# Audio_Codec.net
KiCad netlist of a schematic drawn in Altium Designer
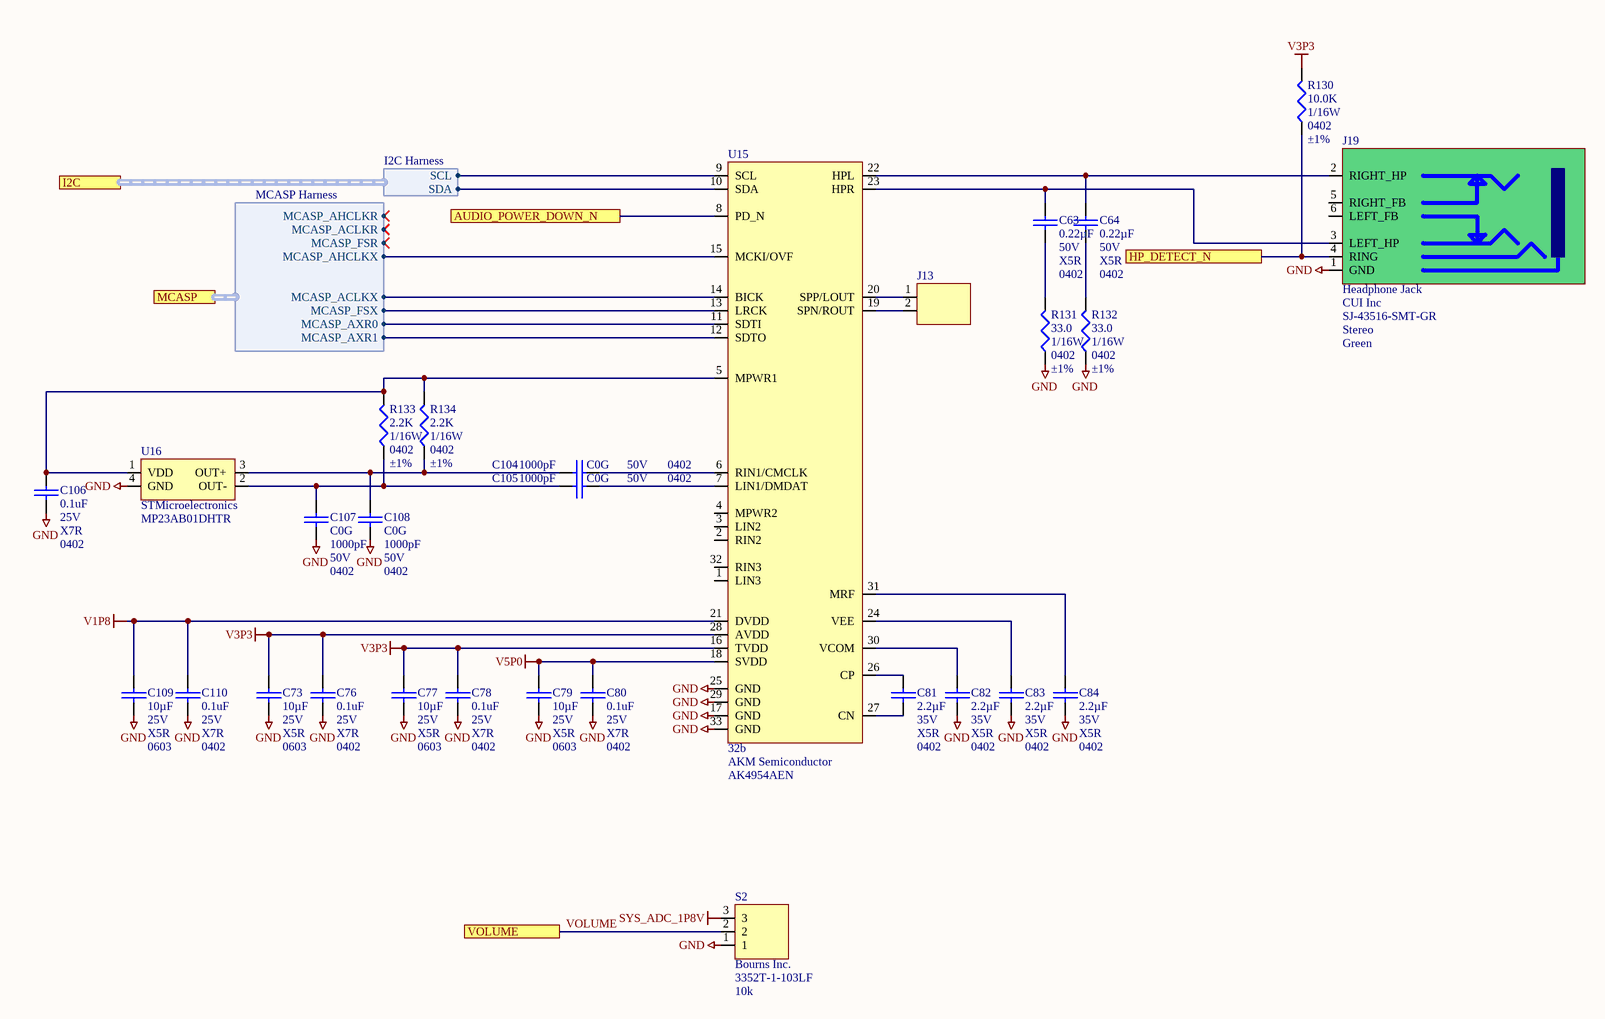
[diagram p0: Audio Codec.SchDoc]

(export (version "E")
  (design (tool "Eeschema 10.0.6"))
  (components
    (comp (ref "C63")
      (value "C_0402_0.22UF_50V")
      (footprint "C_0402")
      (description "CAP CER 0.22UF 50V X5R 0402")
      (fields
        (field (name "MANUFACTURER") "Taiyo Yuden")
        (field (name "MANUFACTURER PART NUMBER") "UMK105BJ224KV-F")
        (field (name "CAPACITANCE") "0.22µF")
        (field (name "VOLTAGE - RATED") "50V")
        (field (name "TEMPERATURE COEFFICIENT") "X5R")
        (field (name "PACKAGE / CASE") "0402")
      )
      (libsource (lib "Main Library") (part "C_0402_0.22UF_50V"))
    )
    (comp (ref "C64")
      (value "C_0402_0.22UF_50V")
      (footprint "C_0402")
      (description "CAP CER 0.22UF 50V X5R 0402")
      (fields
        (field (name "MANUFACTURER") "Taiyo Yuden")
        (field (name "MANUFACTURER PART NUMBER") "UMK105BJ224KV-F")
        (field (name "CAPACITANCE") "0.22µF")
        (field (name "VOLTAGE - RATED") "50V")
        (field (name "TEMPERATURE COEFFICIENT") "X5R")
        (field (name "PACKAGE / CASE") "0402")
      )
      (libsource (lib "Main Library") (part "C_0402_0.22UF_50V"))
    )
    (comp (ref "C73")
      (value "C_0603_10µF")
      (footprint "C_ERA-0603")
      (description "CAP CER 10UF 16V X5R 0603")
      (fields
        (field (name "MANUFACTURER") "Murata Electronics North America")
        (field (name "MANUFACTURER PART NUMBER") "GRM188R61C106MA73D")
        (field (name "CAPACITANCE") "10µF")
        (field (name "VOLTAGE - RATED") "25V")
        (field (name "TEMPERATURE COEFFICIENT") "X5R")
        (field (name "PACKAGE / CASE") "0603")
      )
      (libsource (lib "Cospan Design") (part "C_0603_10µF"))
    )
    (comp (ref "C76")
      (value "C_0402_0.1UF_25V")
      (footprint "C_0402")
      (description "CAP CER 0.1UF 25V X6S 0402")
      (fields
        (field (name "TOLERANCE") "10%")
        (field (name "CAPACITANCE") "0.1uF")
        (field (name "VOLTAGE - RATED") "25V")
        (field (name "TEMPERATURE COEFFICIENT") "X7R")
        (field (name "PACKAGE / CASE") "0402")
      )
      (libsource (lib "Cospan Design") (part "C_0402_0.1UF_25V"))
    )
    (comp (ref "C77")
      (value "C_0603_10µF")
      (footprint "C_ERA-0603")
      (description "CAP CER 10UF 16V X5R 0603")
      (fields
        (field (name "MANUFACTURER") "Murata Electronics North America")
        (field (name "MANUFACTURER PART NUMBER") "GRM188R61C106MA73D")
        (field (name "CAPACITANCE") "10µF")
        (field (name "VOLTAGE - RATED") "25V")
        (field (name "TEMPERATURE COEFFICIENT") "X5R")
        (field (name "PACKAGE / CASE") "0603")
      )
      (libsource (lib "Cospan Design") (part "C_0603_10µF"))
    )
    (comp (ref "C78")
      (value "C_0402_0.1UF_25V")
      (footprint "C_0402")
      (description "CAP CER 0.1UF 25V X6S 0402")
      (fields
        (field (name "TOLERANCE") "10%")
        (field (name "CAPACITANCE") "0.1uF")
        (field (name "VOLTAGE - RATED") "25V")
        (field (name "TEMPERATURE COEFFICIENT") "X7R")
        (field (name "PACKAGE / CASE") "0402")
      )
      (libsource (lib "Cospan Design") (part "C_0402_0.1UF_25V"))
    )
    (comp (ref "C79")
      (value "C_0603_10µF")
      (footprint "C_ERA-0603")
      (description "CAP CER 10UF 16V X5R 0603")
      (fields
        (field (name "MANUFACTURER") "Murata Electronics North America")
        (field (name "MANUFACTURER PART NUMBER") "GRM188R61C106MA73D")
        (field (name "CAPACITANCE") "10µF")
        (field (name "VOLTAGE - RATED") "25V")
        (field (name "TEMPERATURE COEFFICIENT") "X5R")
        (field (name "PACKAGE / CASE") "0603")
      )
      (libsource (lib "Cospan Design") (part "C_0603_10µF"))
    )
    (comp (ref "C80")
      (value "C_0402_0.1UF_25V")
      (footprint "C_0402")
      (description "CAP CER 0.1UF 25V X6S 0402")
      (fields
        (field (name "TOLERANCE") "10%")
        (field (name "CAPACITANCE") "0.1uF")
        (field (name "VOLTAGE - RATED") "25V")
        (field (name "TEMPERATURE COEFFICIENT") "X7R")
        (field (name "PACKAGE / CASE") "0402")
      )
      (libsource (lib "Cospan Design") (part "C_0402_0.1UF_25V"))
    )
    (comp (ref "C81")
      (value "C_0402_2.2uF_35V")
      (footprint "C_0402")
      (description "CAP CER 2.2UF 35V 20% X5R 0402")
      (fields
        (field (name "MANUFACTURER") "TDK Corporation")
        (field (name "MANUFACTURER PART NUMBER") "C1005X5R1V225K050BC")
        (field (name "CAPACITANCE") "2.2µF")
        (field (name "VOLTAGE - RATED") "35V")
        (field (name "TEMPERATURE COEFFICIENT") "X5R")
        (field (name "PACKAGE / CASE") "0402")
      )
      (libsource (lib "Main Library") (part "C_0402_2.2uF_35V"))
    )
    (comp (ref "C82")
      (value "C_0402_2.2uF_35V")
      (footprint "C_0402")
      (description "CAP CER 2.2UF 35V 20% X5R 0402")
      (fields
        (field (name "MANUFACTURER") "TDK Corporation")
        (field (name "MANUFACTURER PART NUMBER") "C1005X5R1V225K050BC")
        (field (name "CAPACITANCE") "2.2µF")
        (field (name "VOLTAGE - RATED") "35V")
        (field (name "TEMPERATURE COEFFICIENT") "X5R")
        (field (name "PACKAGE / CASE") "0402")
      )
      (libsource (lib "Main Library") (part "C_0402_2.2uF_35V"))
    )
    (comp (ref "C83")
      (value "C_0402_2.2uF_35V")
      (footprint "C_0402")
      (description "CAP CER 2.2UF 35V 20% X5R 0402")
      (fields
        (field (name "MANUFACTURER") "TDK Corporation")
        (field (name "MANUFACTURER PART NUMBER") "C1005X5R1V225K050BC")
        (field (name "CAPACITANCE") "2.2µF")
        (field (name "VOLTAGE - RATED") "35V")
        (field (name "TEMPERATURE COEFFICIENT") "X5R")
        (field (name "PACKAGE / CASE") "0402")
      )
      (libsource (lib "Main Library") (part "C_0402_2.2uF_35V"))
    )
    (comp (ref "C84")
      (value "C_0402_2.2uF_35V")
      (footprint "C_0402")
      (description "CAP CER 2.2UF 35V 20% X5R 0402")
      (fields
        (field (name "MANUFACTURER") "TDK Corporation")
        (field (name "MANUFACTURER PART NUMBER") "C1005X5R1V225K050BC")
        (field (name "CAPACITANCE") "2.2µF")
        (field (name "VOLTAGE - RATED") "35V")
        (field (name "TEMPERATURE COEFFICIENT") "X5R")
        (field (name "PACKAGE / CASE") "0402")
      )
      (libsource (lib "Main Library") (part "C_0402_2.2uF_35V"))
    )
    (comp (ref "C104")
      (value "1000pF")
      (footprint "C_0402")
      (description "CAP CER 1000PF 50V C0G 0402")
      (fields
        (field (name "MANUFACTURER") "Murata Electronics North America")
        (field (name "MANUFACTURER PART NUMBER") "GRM1555C1H102JA01D")
        (field (name "TEMPERATURE COEFFICIENT") "C0G")
        (field (name "CAPACITANCE") "1000pF")
        (field (name "VOLTAGE - RATED") "50V")
        (field (name "PACKAGE / CASE") "0402")
      )
      (libsource (lib "Main Library") (part "C_0402_1000PF_50V"))
    )
    (comp (ref "C105")
      (value "1000pF")
      (footprint "C_0402")
      (description "CAP CER 1000PF 50V C0G 0402")
      (fields
        (field (name "MANUFACTURER") "Murata Electronics North America")
        (field (name "MANUFACTURER PART NUMBER") "GRM1555C1H102JA01D")
        (field (name "TEMPERATURE COEFFICIENT") "C0G")
        (field (name "CAPACITANCE") "1000pF")
        (field (name "VOLTAGE - RATED") "50V")
        (field (name "PACKAGE / CASE") "0402")
      )
      (libsource (lib "Main Library") (part "C_0402_1000PF_50V"))
    )
    (comp (ref "C106")
      (value "C_0402_0.1UF_25V")
      (footprint "C_0402")
      (description "CAP CER 0.1UF 25V X6S 0402")
      (fields
        (field (name "TOLERANCE") "10%")
        (field (name "CAPACITANCE") "0.1uF")
        (field (name "VOLTAGE - RATED") "25V")
        (field (name "TEMPERATURE COEFFICIENT") "X7R")
        (field (name "PACKAGE / CASE") "0402")
      )
      (libsource (lib "Cospan Design") (part "C_0402_0.1UF_25V"))
    )
    (comp (ref "C107")
      (value "1000pF")
      (footprint "C_0402")
      (description "CAP CER 1000PF 50V C0G 0402")
      (fields
        (field (name "MANUFACTURER") "Murata Electronics North America")
        (field (name "MANUFACTURER PART NUMBER") "GRM1555C1H102JA01D")
        (field (name "TEMPERATURE COEFFICIENT") "C0G")
        (field (name "CAPACITANCE") "1000pF")
        (field (name "VOLTAGE - RATED") "50V")
        (field (name "PACKAGE / CASE") "0402")
      )
      (libsource (lib "Main Library") (part "C_0402_1000PF_50V"))
    )
    (comp (ref "C108")
      (value "1000pF")
      (footprint "C_0402")
      (description "CAP CER 1000PF 50V C0G 0402")
      (fields
        (field (name "MANUFACTURER") "Murata Electronics North America")
        (field (name "MANUFACTURER PART NUMBER") "GRM1555C1H102JA01D")
        (field (name "TEMPERATURE COEFFICIENT") "C0G")
        (field (name "CAPACITANCE") "1000pF")
        (field (name "VOLTAGE - RATED") "50V")
        (field (name "PACKAGE / CASE") "0402")
      )
      (libsource (lib "Main Library") (part "C_0402_1000PF_50V"))
    )
    (comp (ref "C109")
      (value "C_0603_10µF")
      (footprint "C_ERA-0603")
      (description "CAP CER 10UF 16V X5R 0603")
      (fields
        (field (name "MANUFACTURER") "Murata Electronics North America")
        (field (name "MANUFACTURER PART NUMBER") "GRM188R61C106MA73D")
        (field (name "CAPACITANCE") "10µF")
        (field (name "VOLTAGE - RATED") "25V")
        (field (name "TEMPERATURE COEFFICIENT") "X5R")
        (field (name "PACKAGE / CASE") "0603")
      )
      (libsource (lib "Cospan Design") (part "C_0603_10µF"))
    )
    (comp (ref "C110")
      (value "C_0402_0.1UF_25V")
      (footprint "C_0402")
      (description "CAP CER 0.1UF 25V X6S 0402")
      (fields
        (field (name "TOLERANCE") "10%")
        (field (name "CAPACITANCE") "0.1uF")
        (field (name "VOLTAGE - RATED") "25V")
        (field (name "TEMPERATURE COEFFICIENT") "X7R")
        (field (name "PACKAGE / CASE") "0402")
      )
      (libsource (lib "Cospan Design") (part "C_0402_0.1UF_25V"))
    )
    (comp (ref "J13")
      (value "2 Holes")
      (footprint "1X2_HOLES")
      (libsource (lib "Main Library") (part "J_1X2_HOLES"))
    )
    (comp (ref "J19")
      (value "Headphone Jack")
      (footprint "HEADPHONE_JACK")
      (description "CONN AUDIO JACK 3.5MM 4COND SMD")
      (fields
        (field (name "MANUFACTURER") "CUI Inc")
        (field (name "MANUFACTURER PART NUMBER") "SJ-43516-SMT-GR")
        (field (name "SIGNAL LINES") "Stereo")
        (field (name "COLOR") "Green")
      )
      (libsource (lib "Main Library") (part "J_HEADPHONE_JACK"))
    )
    (comp (ref "R130")
      (value "R_0402_10.0K")
      (footprint "R_0402")
      (description "RES 10.0K OHM 1/16W 1% 0402 SMD")
      (fields
        (field (name "MANUFACTURER") "Stackpole Electronics Inc")
        (field (name "MANUFACTURER PART NUMBER") "RMCF0402FT10K0")
        (field (name "RESISTANCE IN OHMS") "10.0K")
        (field (name "POWER (WATTS)") "1/16W")
        (field (name "CASE") "0402")
        (field (name "TOLERANCE") "±1%")
      )
      (libsource (lib "Main Library") (part "R_0402_10.0K"))
    )
    (comp (ref "R131")
      (value "R_0402_33")
      (footprint "R_0402")
      (description "RES 33.0 OHM 1/16W 1% 0402 SMD")
      (fields
        (field (name "MANUFACTURER") "Yageo")
        (field (name "MANUFACTURER PART NUMBER") "RC0402FR-0733RL")
        (field (name "RESISTANCE IN OHMS") "33.0")
        (field (name "POWER (WATTS)") "1/16W")
        (field (name "CASE") "0402")
        (field (name "TOLERANCE") "±1%")
      )
      (libsource (lib "Main Library") (part "R_0402_33"))
    )
    (comp (ref "R132")
      (value "R_0402_33")
      (footprint "R_0402")
      (description "RES 33.0 OHM 1/16W 1% 0402 SMD")
      (fields
        (field (name "MANUFACTURER") "Yageo")
        (field (name "MANUFACTURER PART NUMBER") "RC0402FR-0733RL")
        (field (name "RESISTANCE IN OHMS") "33.0")
        (field (name "POWER (WATTS)") "1/16W")
        (field (name "CASE") "0402")
        (field (name "TOLERANCE") "±1%")
      )
      (libsource (lib "Main Library") (part "R_0402_33"))
    )
    (comp (ref "R133")
      (value "R_0402_2.2K")
      (footprint "R_0402")
      (description "RES SMD 2.2K OHM 1% 1/10W 0402")
      (fields
        (field (name "MANUFACTURER") "Panasonic Electronic Components")
        (field (name "MANUFACTURER PART NUMBER") "ERJ-2RKF2201X")
        (field (name "RESISTANCE IN OHMS") "2.2K")
        (field (name "POWER (WATTS)") "1/16W")
        (field (name "CASE") "0402")
        (field (name "TOLERANCE") "±1%")
      )
      (libsource (lib "Cospan Design") (part "R_0402_2.2K"))
    )
    (comp (ref "R134")
      (value "R_0402_2.2K")
      (footprint "R_0402")
      (description "RES SMD 2.2K OHM 1% 1/10W 0402")
      (fields
        (field (name "MANUFACTURER") "Panasonic Electronic Components")
        (field (name "MANUFACTURER PART NUMBER") "ERJ-2RKF2201X")
        (field (name "RESISTANCE IN OHMS") "2.2K")
        (field (name "POWER (WATTS)") "1/16W")
        (field (name "CASE") "0402")
        (field (name "TOLERANCE") "±1%")
      )
      (libsource (lib "Cospan Design") (part "R_0402_2.2K"))
    )
    (comp (ref "S2")
      (value "SLIDE POT")
      (footprint "HDR_1X3_POT")
      (description "POT 10K OHM THUMBWHEEL CERM ST")
      (fields
        (field (name "TOLERANCE") "±20%")
        (field (name "MANUFACTURER") "Bourns Inc.")
        (field (name "MANUFACTURER PART NUMBER") "3352T-1-103LF")
        (field (name "RESISTANCE (OHMS)") "10k")
      )
      (libsource (lib "Main Library") (part "S_3352T-1-103LF"))
    )
    (comp (ref "U15")
      (value "U_AK4954AEN")
      (footprint "QFN40P400X400X80_HS-33N")
      (description "IC STEREO CODEC 32BIT 32QFN")
      (fields
        (field (name "RESOLUTION") "32b")
        (field (name "MANUFACTURER 1") "AKM Semiconductor")
        (field (name "MANUFACTURER PART NUMBER 1") "AK4954AEN")
      )
      (libsource (lib "Cospan Design") (part "U_AK4954AEN"))
    )
    (comp (ref "U16")
      (value "U_MP23AB01DHTR")
      (footprint "RHLGA")
      (description "MIC MEMS ANALOG OMNI -38DB")
      (fields
        (field (name "MANUFACTURER 1") "STMicroelectronics")
        (field (name "MANUFACTURER PART NUMBER 1") "MP23AB01DHTR")
      )
      (libsource (lib "Cospan Design") (part "U_MP23AB01DHTR"))
    )
  )
  (nets
    (net (code "4") (name "/AUDIO_POWER_DOWN_N") (class "Default")
      (node (ref "U15") (pin "8") (pinfunction "PD_N_8") (pintype "passive"))
    )
    (net (code "5") (name "/HP_DETECT_N") (class "Default")
      (node (ref "J19") (pin "4") (pinfunction "RING_4") (pintype "passive"))
      (node (ref "R130") (pin "2") (pinfunction "2_2") (pintype "passive"))
    )
    (net (code "6") (name "/MCASP_ACLKX") (class "Default")
      (node (ref "U15") (pin "14") (pinfunction "BICK_14") (pintype "passive"))
    )
    (net (code "7") (name "/MCASP_AHCLKX") (class "Default")
      (node (ref "U15") (pin "15") (pinfunction "MCKI/OVF_15") (pintype "passive"))
    )
    (net (code "8") (name "/MCASP_AXR0") (class "Default")
      (node (ref "U15") (pin "11") (pinfunction "SDTI_11") (pintype "passive"))
    )
    (net (code "9") (name "/MCASP_AXR1") (class "Default")
      (node (ref "U15") (pin "12") (pinfunction "SDTO_12") (pintype "passive"))
    )
    (net (code "10") (name "/MCASP_FSX") (class "Default")
      (node (ref "U15") (pin "13") (pinfunction "LRCK_13") (pintype "passive"))
    )
    (net (code "11") (name "/SCL") (class "Default")
      (node (ref "U15") (pin "9") (pinfunction "SCL_9") (pintype "passive"))
    )
    (net (code "12") (name "/SDA") (class "Default")
      (node (ref "U15") (pin "10") (pinfunction "SDA_10") (pintype "passive"))
    )
    (net (code "13") (name "/VOLUME") (class "Default")
      (node (ref "S2") (pin "2") (pinfunction "2_2") (pintype "passive"))
    )
    (net (code "16") (name "GND") (class "Default")
      (node (ref "C106") (pin "1") (pinfunction "1_1") (pintype "passive"))
      (node (ref "C107") (pin "2") (pinfunction "2_2") (pintype "passive"))
      (node (ref "C108") (pin "2") (pinfunction "2_2") (pintype "passive"))
      (node (ref "C109") (pin "1") (pinfunction "1_1") (pintype "passive"))
      (node (ref "C110") (pin "1") (pinfunction "1_1") (pintype "passive"))
      (node (ref "C73") (pin "1") (pinfunction "1_1") (pintype "passive"))
      (node (ref "C76") (pin "1") (pinfunction "1_1") (pintype "passive"))
      (node (ref "C77") (pin "1") (pinfunction "1_1") (pintype "passive"))
      (node (ref "C78") (pin "1") (pinfunction "1_1") (pintype "passive"))
      (node (ref "C79") (pin "1") (pinfunction "1_1") (pintype "passive"))
      (node (ref "C80") (pin "1") (pinfunction "1_1") (pintype "passive"))
      (node (ref "C82") (pin "1") (pinfunction "1_1") (pintype "passive"))
      (node (ref "C83") (pin "1") (pinfunction "1_1") (pintype "passive"))
      (node (ref "C84") (pin "1") (pinfunction "1_1") (pintype "passive"))
      (node (ref "J19") (pin "1") (pinfunction "GND_1") (pintype "passive"))
      (node (ref "R131") (pin "2") (pinfunction "2_2") (pintype "passive"))
      (node (ref "R132") (pin "2") (pinfunction "2_2") (pintype "passive"))
      (node (ref "S2") (pin "1") (pinfunction "1_1") (pintype "passive"))
      (node (ref "U15") (pin "17") (pinfunction "GND_17") (pintype "passive"))
      (node (ref "U15") (pin "25") (pinfunction "GND_25") (pintype "passive"))
      (node (ref "U15") (pin "29") (pinfunction "GND_29") (pintype "passive"))
      (node (ref "U15") (pin "33") (pinfunction "GND_33") (pintype "passive"))
      (node (ref "U16") (pin "4") (pinfunction "GND_4") (pintype "passive"))
    )
    (net (code "17") (name "Net-(C63-Pad1)") (class "Default")
      (node (ref "C63") (pin "1") (pinfunction "1_1") (pintype "passive"))
      (node (ref "R131") (pin "1") (pinfunction "1_1") (pintype "passive"))
    )
    (net (code "18") (name "Net-(C64-Pad1)") (class "Default")
      (node (ref "C64") (pin "1") (pinfunction "1_1") (pintype "passive"))
      (node (ref "R132") (pin "1") (pinfunction "1_1") (pintype "passive"))
    )
    (net (code "19") (name "Net-(J19-LEFT_HP)") (class "Default")
      (node (ref "C63") (pin "2") (pinfunction "2_2") (pintype "passive"))
      (node (ref "J19") (pin "3") (pinfunction "LEFT_HP_3") (pintype "passive"))
      (node (ref "U15") (pin "23") (pinfunction "HPR_23") (pintype "passive"))
    )
    (net (code "20") (name "Net-(J19-RIGHT_HP)") (class "Default")
      (node (ref "C64") (pin "2") (pinfunction "2_2") (pintype "passive"))
      (node (ref "J19") (pin "2") (pinfunction "RIGHT_HP_2") (pintype "passive"))
      (node (ref "U15") (pin "22") (pinfunction "HPL_22") (pintype "passive"))
    )
    (net (code "21") (name "Net-(U15-CN)") (class "Default")
      (node (ref "C81") (pin "1") (pinfunction "1_1") (pintype "passive"))
      (node (ref "U15") (pin "27") (pinfunction "CN_27") (pintype "passive"))
    )
    (net (code "22") (name "Net-(U15-CP)") (class "Default")
      (node (ref "C81") (pin "2") (pinfunction "2_2") (pintype "passive"))
      (node (ref "U15") (pin "26") (pinfunction "CP_26") (pintype "passive"))
    )
    (net (code "23") (name "Net-(U15-LIN1{slash}DMDAT)") (class "Default")
      (node (ref "C105") (pin "1") (pinfunction "1_1") (pintype "passive"))
      (node (ref "U15") (pin "7") (pinfunction "LIN1/DMDAT_7") (pintype "passive"))
    )
    (net (code "24") (name "Net-(U15-MPWR1)") (class "Default")
      (node (ref "C106") (pin "2") (pinfunction "2_2") (pintype "passive"))
      (node (ref "R133") (pin "1") (pinfunction "1_1") (pintype "passive"))
      (node (ref "R134") (pin "1") (pinfunction "1_1") (pintype "passive"))
      (node (ref "U15") (pin "5") (pinfunction "MPWR1_5") (pintype "passive"))
      (node (ref "U16") (pin "1") (pinfunction "VDD_1") (pintype "passive"))
    )
    (net (code "25") (name "Net-(U15-MRF)") (class "Default")
      (node (ref "C84") (pin "2") (pinfunction "2_2") (pintype "passive"))
      (node (ref "U15") (pin "31") (pinfunction "MRF_31") (pintype "passive"))
    )
    (net (code "26") (name "Net-(U15-RIN1{slash}CMCLK)") (class "Default")
      (node (ref "C104") (pin "1") (pinfunction "1_1") (pintype "passive"))
      (node (ref "U15") (pin "6") (pinfunction "RIN1/CMCLK_6") (pintype "passive"))
    )
    (net (code "27") (name "Net-(U15-SPN{slash}ROUT)") (class "Default")
      (node (ref "J13") (pin "2") (pinfunction "2_2") (pintype "passive"))
      (node (ref "U15") (pin "19") (pinfunction "SPN/ROUT_19") (pintype "passive"))
    )
    (net (code "28") (name "Net-(U15-SPP{slash}LOUT)") (class "Default")
      (node (ref "J13") (pin "1") (pinfunction "1_1") (pintype "passive"))
      (node (ref "U15") (pin "20") (pinfunction "SPP/LOUT_20") (pintype "passive"))
    )
    (net (code "29") (name "Net-(U15-VCOM)") (class "Default")
      (node (ref "C82") (pin "2") (pinfunction "2_2") (pintype "passive"))
      (node (ref "U15") (pin "30") (pinfunction "VCOM_30") (pintype "passive"))
    )
    (net (code "30") (name "Net-(U15-VEE)") (class "Default")
      (node (ref "C83") (pin "2") (pinfunction "2_2") (pintype "passive"))
      (node (ref "U15") (pin "24") (pinfunction "VEE_24") (pintype "passive"))
    )
    (net (code "31") (name "Net-(U16-OUT+)") (class "Default")
      (node (ref "C104") (pin "2") (pinfunction "2_2") (pintype "passive"))
      (node (ref "C108") (pin "1") (pinfunction "1_1") (pintype "passive"))
      (node (ref "R134") (pin "2") (pinfunction "2_2") (pintype "passive"))
      (node (ref "U16") (pin "3") (pinfunction "OUT+_3") (pintype "passive"))
    )
    (net (code "32") (name "Net-(U16-OUT-)") (class "Default")
      (node (ref "C105") (pin "2") (pinfunction "2_2") (pintype "passive"))
      (node (ref "C107") (pin "1") (pinfunction "1_1") (pintype "passive"))
      (node (ref "R133") (pin "2") (pinfunction "2_2") (pintype "passive"))
      (node (ref "U16") (pin "2") (pinfunction "OUT-_2") (pintype "passive"))
    )
    (net (code "33") (name "SYS_ADC_1P8V") (class "Default")
      (node (ref "S2") (pin "3") (pinfunction "3_3") (pintype "passive"))
    )
    (net (code "34") (name "V1P8") (class "Default")
      (node (ref "C109") (pin "2") (pinfunction "2_2") (pintype "passive"))
      (node (ref "C110") (pin "2") (pinfunction "2_2") (pintype "passive"))
      (node (ref "U15") (pin "21") (pinfunction "DVDD_21") (pintype "passive"))
    )
    (net (code "35") (name "V3P3") (class "Default")
      (node (ref "C73") (pin "2") (pinfunction "2_2") (pintype "passive"))
      (node (ref "C76") (pin "2") (pinfunction "2_2") (pintype "passive"))
      (node (ref "C77") (pin "2") (pinfunction "2_2") (pintype "passive"))
      (node (ref "C78") (pin "2") (pinfunction "2_2") (pintype "passive"))
      (node (ref "R130") (pin "1") (pinfunction "1_1") (pintype "passive"))
      (node (ref "U15") (pin "16") (pinfunction "TVDD_16") (pintype "passive"))
      (node (ref "U15") (pin "28") (pinfunction "AVDD_28") (pintype "passive"))
    )
    (net (code "36") (name "V5P0") (class "Default")
      (node (ref "C79") (pin "2") (pinfunction "2_2") (pintype "passive"))
      (node (ref "C80") (pin "2") (pinfunction "2_2") (pintype "passive"))
      (node (ref "U15") (pin "18") (pinfunction "SVDD_18") (pintype "passive"))
    )
    (net (code "37") (name "unconnected-(J19-LEFT_FB-Pad6)") (class "Default")
      (node (ref "J19") (pin "6") (pinfunction "LEFT_FB_6") (pintype "passive"))
    )
    (net (code "38") (name "unconnected-(J19-RIGHT_FB-Pad5)") (class "Default")
      (node (ref "J19") (pin "5") (pinfunction "RIGHT_FB_5") (pintype "passive"))
    )
    (net (code "39") (name "unconnected-(U15-LIN2-Pad3)") (class "Default")
      (node (ref "U15") (pin "3") (pinfunction "LIN2_3") (pintype "passive"))
    )
    (net (code "40") (name "unconnected-(U15-LIN3-Pad1)") (class "Default")
      (node (ref "U15") (pin "1") (pinfunction "LIN3_1") (pintype "passive"))
    )
    (net (code "41") (name "unconnected-(U15-MPWR2-Pad4)") (class "Default")
      (node (ref "U15") (pin "4") (pinfunction "MPWR2_4") (pintype "passive"))
    )
    (net (code "42") (name "unconnected-(U15-RIN2-Pad2)") (class "Default")
      (node (ref "U15") (pin "2") (pinfunction "RIN2_2") (pintype "passive"))
    )
    (net (code "43") (name "unconnected-(U15-RIN3-Pad32)") (class "Default")
      (node (ref "U15") (pin "32") (pinfunction "RIN3_32") (pintype "passive"))
    )
  )
)
